# MRCS-QandD-Carbon-Mic-Adapter.net
KiCad netlist of a schematic drawn in EAGLE
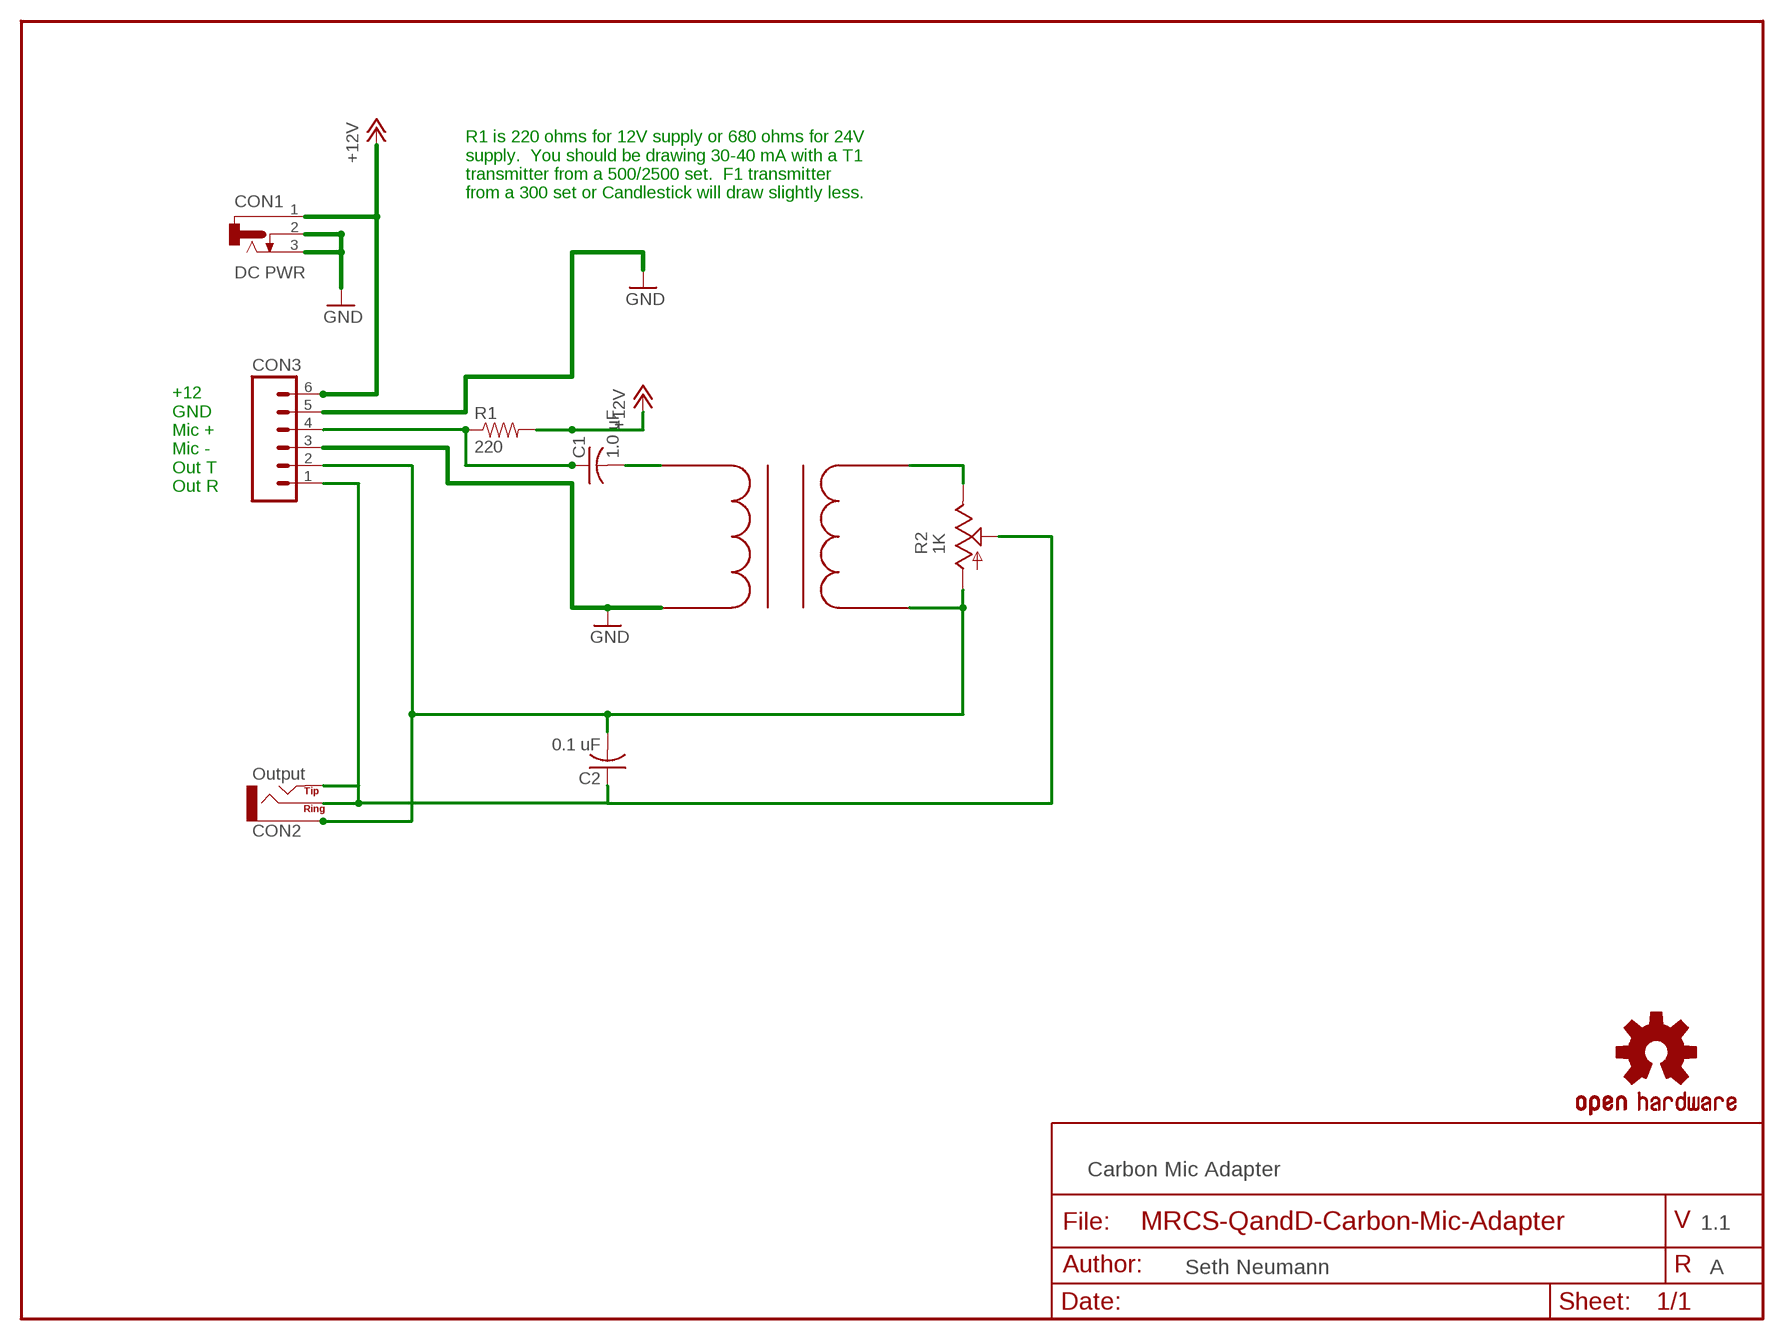
[diagram p0: schematic, sheet 1]

(export (version "E")
  (design (tool "Eeschema 10.0.6"))
  (components
    (comp (ref "C1")
      (value "1.0 uF")
      (footprint "eagle-import:C-PTH-0.100")
      (libsource (lib "eagle-import") (part "CAPPTH2"))
    )
    (comp (ref "C2")
      (value "0.1 uF")
      (footprint "eagle-import:C-PTH-0.100")
      (libsource (lib "eagle-import") (part "CAPPTH2"))
    )
    (comp (ref "CON1")
      (value "DC PWR")
      (footprint "eagle-import:DCJ0202")
      (libsource (lib "eagle-import") (part "CONNECTOR-DC-POWER-RA"))
    )
    (comp (ref "CON2")
      (value "Output")
      (footprint "eagle-import:AUDIO-JACK-3.5MM_STEREO")
      (libsource (lib "eagle-import") (part "CONNECTOR-AUDIO3.5MM-ADAMTECH"))
    )
    (comp (ref "CON3")
      (value "CONNECTOR-M063.5MM-6")
      (footprint "eagle-import:SCREWTERMINAL-3.5MM-6")
      (libsource (lib "eagle-import") (part "CONNECTOR-M063.5MM-6"))
    )
    (comp (ref "OSHW1")
      (value "DOC-OSHW-LOGO-M")
      (footprint "eagle-import:OSHW-LOGO-M")
      (libsource (lib "eagle-import") (part "DOC-OSHW-LOGO-M"))
    )
    (comp (ref "R1")
      (value "220")
      (footprint "eagle-import:AXIAL-0.4-RES")
      (libsource (lib "eagle-import") (part "RPTH04"))
    )
    (comp (ref "R2")
      (value "1K")
      (footprint "eagle-import:RS3")
      (libsource (lib "eagle-import") (part "TRIM_US-RS3"))
    )
    (comp (ref "U$1")
      (value "EI14_600-600")
      (footprint "eagle-import:XFMR580X500")
      (libsource (lib "eagle-import") (part "EI14_600-600"))
    )
  )
  (nets
    (net (code "1") (name "+12V") (class "Default")
      (node (ref "CON1") (pin "1") (pinfunction "1_1") (pintype "passive"))
      (node (ref "CON3") (pin "6") (pinfunction "6_6") (pintype "passive"))
      (node (ref "R1") (pin "P$2") (pinfunction "2_P$2") (pintype "passive"))
    )
    (net (code "2") (name "GND") (class "Default")
      (node (ref "CON1") (pin "2") (pinfunction "2_2") (pintype "passive"))
      (node (ref "CON1") (pin "3") (pinfunction "3_3") (pintype "passive"))
      (node (ref "CON3") (pin "3") (pinfunction "3_3") (pintype "passive"))
      (node (ref "CON3") (pin "5") (pinfunction "5_5") (pintype "passive"))
      (node (ref "U$1") (pin "PBOTTOM") (pinfunction "PBOTTOM_PBOTTOM") (pintype "bidirectional"))
    )
    (net (code "3") (name "Net-(C1-Pad2)") (class "Default")
      (node (ref "C1") (pin "2") (pinfunction "2_2") (pintype "passive"))
      (node (ref "U$1") (pin "PTOP") (pinfunction "PTOP_PTOP") (pintype "bidirectional"))
    )
    (net (code "4") (name "Net-(C2-Pad1)") (class "Default")
      (node (ref "C2") (pin "1") (pinfunction "1_1") (pintype "passive"))
      (node (ref "CON2") (pin "RING") (pinfunction "RING_RING") (pintype "bidirectional"))
      (node (ref "CON2") (pin "TIP") (pinfunction "TIP_TIP") (pintype "bidirectional"))
      (node (ref "CON3") (pin "1") (pinfunction "1_1") (pintype "passive"))
      (node (ref "R2") (pin "S") (pinfunction "S_S") (pintype "passive"))
    )
    (net (code "5") (name "Net-(CON2-SLEEVE)") (class "Default")
      (node (ref "C2") (pin "2") (pinfunction "2_2") (pintype "passive"))
      (node (ref "CON2") (pin "GND") (pinfunction "SLEEVE_GND") (pintype "bidirectional"))
      (node (ref "CON3") (pin "2") (pinfunction "2_2") (pintype "passive"))
      (node (ref "R2") (pin "A") (pinfunction "A_A") (pintype "passive"))
      (node (ref "U$1") (pin "SBOTTOM") (pinfunction "SBOTTOM_SBOTTOM") (pintype "bidirectional"))
    )
    (net (code "6") (name "Net-(R1-1)") (class "Default")
      (node (ref "C1") (pin "1") (pinfunction "1_1") (pintype "passive"))
      (node (ref "CON3") (pin "4") (pinfunction "4_4") (pintype "passive"))
      (node (ref "R1") (pin "P$1") (pinfunction "1_P$1") (pintype "passive"))
    )
    (net (code "7") (name "Net-(R2-PadE)") (class "Default")
      (node (ref "R2") (pin "E") (pinfunction "E_E") (pintype "passive"))
      (node (ref "U$1") (pin "STOP") (pinfunction "STOP_STOP") (pintype "bidirectional"))
    )
  )
)
